# minime_2_1.net
KiCad netlist of a schematic drawn in EAGLE
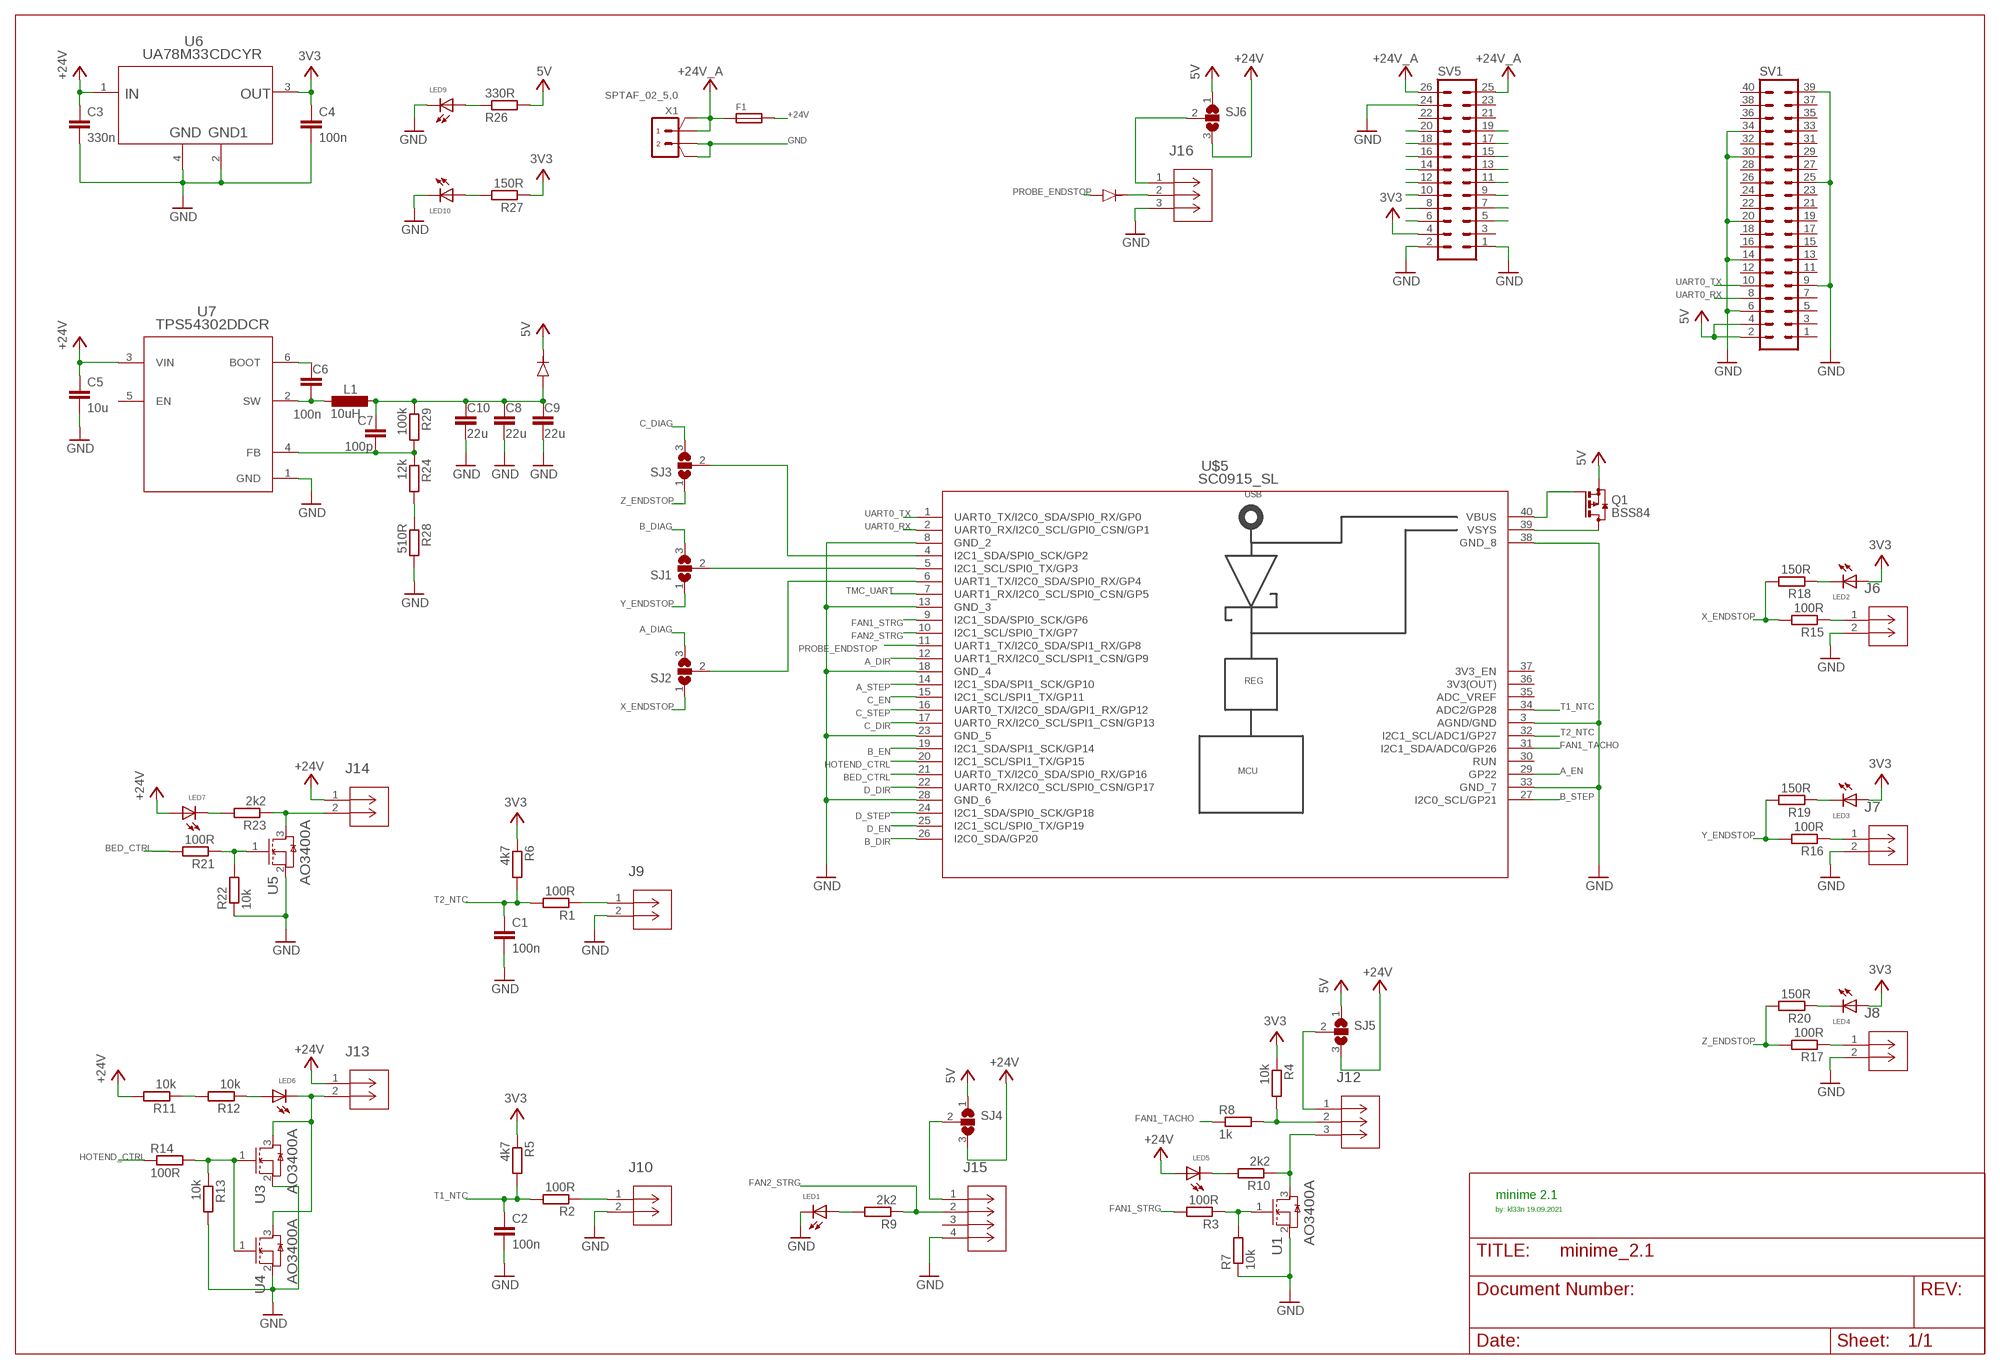
[diagram p0: schematic, sheet 1]

(export (version "E")
  (design (tool "Eeschema 10.0.6"))
  (components
    (comp (ref "C1")
      (value "100n")
      (footprint "eagle-import:C0603")
      (libsource (lib "eagle-import") (part "C-EUC0603"))
    )
    (comp (ref "C2")
      (value "100n")
      (footprint "eagle-import:C0603")
      (libsource (lib "eagle-import") (part "C-EUC0603"))
    )
    (comp (ref "C3")
      (value "330n")
      (footprint "eagle-import:C0603")
      (libsource (lib "eagle-import") (part "C-EUC0603"))
    )
    (comp (ref "C4")
      (value "100n")
      (footprint "eagle-import:C0603")
      (libsource (lib "eagle-import") (part "C-EUC0603"))
    )
    (comp (ref "C5")
      (value "10u")
      (footprint "eagle-import:C0603")
      (libsource (lib "eagle-import") (part "C-EUC0603"))
    )
    (comp (ref "C6")
      (value "100n")
      (footprint "eagle-import:C0603")
      (libsource (lib "eagle-import") (part "C-EUC0603"))
    )
    (comp (ref "C7")
      (value "100p")
      (footprint "eagle-import:C0603")
      (libsource (lib "eagle-import") (part "C-EUC0603"))
    )
    (comp (ref "C8")
      (value "22u")
      (footprint "eagle-import:C0603")
      (libsource (lib "eagle-import") (part "C-EUC0603"))
    )
    (comp (ref "C9")
      (value "22u")
      (footprint "eagle-import:C0603")
      (libsource (lib "eagle-import") (part "C-EUC0603"))
    )
    (comp (ref "C10")
      (value "22u")
      (footprint "eagle-import:C0603")
      (libsource (lib "eagle-import") (part "C-EUC0603"))
    )
    (comp (ref "CR1")
      (value "SS54")
      (footprint "eagle-import:DIODE_DO214AC")
      (fields
        (field (name "MANUFACTURER_PART_NUMBER") "SS14-E3/5AT")
        (field (name "COPYRIGHT") "Copyright (C) 2021 Ultra Librarian. All rights reserved.")
      )
      (libsource (lib "eagle-import") (part "SS14-E3/5AT"))
    )
    (comp (ref "CR2")
      (value "SS14")
      (footprint "eagle-import:DIODE_DO214AC")
      (fields
        (field (name "MANUFACTURER_PART_NUMBER") "SS14-E3/5AT")
        (field (name "COPYRIGHT") "Copyright (C) 2021 Ultra Librarian. All rights reserved.")
      )
      (libsource (lib "eagle-import") (part "SS14-E3/5AT"))
    )
    (comp (ref "F1")
      (value "FUSE/SERIE154")
      (footprint "eagle-import:FUSE_NANO-OMNI")
      (libsource (lib "eagle-import") (part "FUSE/SERIE154"))
    )
    (comp (ref "J6")
      (value "B2B-XH-A(LF)(SN)")
      (footprint "eagle-import:CONN_B2B-XH-A(LF)(SN)_JST")
      (fields (field (name "COPYRIGHT") "Copyright (C) 2018 Accelerated Designs. All rights reserved"))
      (libsource (lib "eagle-import") (part "B2B-XH-A(LF)(SN)"))
    )
    (comp (ref "J7")
      (value "B2B-XH-A(LF)(SN)")
      (footprint "eagle-import:CONN_B2B-XH-A(LF)(SN)_JST")
      (fields (field (name "COPYRIGHT") "Copyright (C) 2018 Accelerated Designs. All rights reserved"))
      (libsource (lib "eagle-import") (part "B2B-XH-A(LF)(SN)"))
    )
    (comp (ref "J8")
      (value "B2B-XH-A(LF)(SN)")
      (footprint "eagle-import:CONN_B2B-XH-A(LF)(SN)_JST")
      (fields (field (name "COPYRIGHT") "Copyright (C) 2018 Accelerated Designs. All rights reserved"))
      (libsource (lib "eagle-import") (part "B2B-XH-A(LF)(SN)"))
    )
    (comp (ref "J9")
      (value "B2B-XH-A(LF)(SN)")
      (footprint "eagle-import:CONN_B2B-XH-A(LF)(SN)_JST")
      (fields (field (name "COPYRIGHT") "Copyright (C) 2018 Accelerated Designs. All rights reserved"))
      (libsource (lib "eagle-import") (part "B2B-XH-A(LF)(SN)"))
    )
    (comp (ref "J10")
      (value "B2B-XH-A(LF)(SN)")
      (footprint "eagle-import:CONN_B2B-XH-A(LF)(SN)_JST")
      (fields (field (name "COPYRIGHT") "Copyright (C) 2018 Accelerated Designs. All rights reserved"))
      (libsource (lib "eagle-import") (part "B2B-XH-A(LF)(SN)"))
    )
    (comp (ref "J12")
      (value "B3B-XH-A(LF)(SN)")
      (footprint "eagle-import:CONN_B3B-XH-A_JST")
      (fields (field (name "COPYRIGHT") "Copyright (C) 2018 Accelerated Designs. All rights reserved"))
      (libsource (lib "eagle-import") (part "B3B-XH-A(LF)(SN)"))
    )
    (comp (ref "J13")
      (value "B2B-XH-A(LF)(SN)")
      (footprint "eagle-import:CONN_B2B-XH-A(LF)(SN)_JST")
      (fields (field (name "COPYRIGHT") "Copyright (C) 2018 Accelerated Designs. All rights reserved"))
      (libsource (lib "eagle-import") (part "B2B-XH-A(LF)(SN)"))
    )
    (comp (ref "J14")
      (value "B2B-XH-A(LF)(SN)")
      (footprint "eagle-import:CONN_B2B-XH-A(LF)(SN)_JST")
      (fields (field (name "COPYRIGHT") "Copyright (C) 2018 Accelerated Designs. All rights reserved"))
      (libsource (lib "eagle-import") (part "B2B-XH-A(LF)(SN)"))
    )
    (comp (ref "J15")
      (value "B4B-XH-AM(LF)(SN)")
      (footprint "eagle-import:CONN_B4B-XH-AM_JST")
      (fields (field (name "COPYRIGHT") "Copyright (C) 2018 Accelerated Designs. All rights reserved"))
      (libsource (lib "eagle-import") (part "B4B-XH-AM(LF)(SN)"))
    )
    (comp (ref "J16")
      (value "B3B-XH-A(LF)(SN)")
      (footprint "eagle-import:CONN_B3B-XH-A_JST")
      (fields (field (name "COPYRIGHT") "Copyright (C) 2018 Accelerated Designs. All rights reserved"))
      (libsource (lib "eagle-import") (part "B3B-XH-A(LF)(SN)"))
    )
    (comp (ref "L1")
      (value "10uH")
      (footprint "eagle-import:POWER-CHOKE_WE-TPC")
      (libsource (lib "eagle-import") (part "L-EUWE-TPC"))
    )
    (comp (ref "LED1")
      (value "LEDCHIP-LED0603")
      (footprint "eagle-import:CHIP-LED0603")
      (libsource (lib "eagle-import") (part "LEDCHIP-LED0603"))
    )
    (comp (ref "LED2")
      (value "LEDCHIP-LED0603")
      (footprint "eagle-import:CHIP-LED0603")
      (libsource (lib "eagle-import") (part "LEDCHIP-LED0603"))
    )
    (comp (ref "LED3")
      (value "LEDCHIP-LED0603")
      (footprint "eagle-import:CHIP-LED0603")
      (libsource (lib "eagle-import") (part "LEDCHIP-LED0603"))
    )
    (comp (ref "LED4")
      (value "LEDCHIP-LED0603")
      (footprint "eagle-import:CHIP-LED0603")
      (libsource (lib "eagle-import") (part "LEDCHIP-LED0603"))
    )
    (comp (ref "LED5")
      (value "LEDCHIP-LED0603")
      (footprint "eagle-import:CHIP-LED0603")
      (libsource (lib "eagle-import") (part "LEDCHIP-LED0603"))
    )
    (comp (ref "LED6")
      (value "LEDCHIP-LED0603")
      (footprint "eagle-import:CHIP-LED0603")
      (libsource (lib "eagle-import") (part "LEDCHIP-LED0603"))
    )
    (comp (ref "LED7")
      (value "LEDCHIP-LED0603")
      (footprint "eagle-import:CHIP-LED0603")
      (libsource (lib "eagle-import") (part "LEDCHIP-LED0603"))
    )
    (comp (ref "LED9")
      (value "LEDCHIP-LED0603")
      (footprint "eagle-import:CHIP-LED0603")
      (libsource (lib "eagle-import") (part "LEDCHIP-LED0603"))
    )
    (comp (ref "LED10")
      (value "LEDCHIP-LED0603")
      (footprint "eagle-import:CHIP-LED0603")
      (libsource (lib "eagle-import") (part "LEDCHIP-LED0603"))
    )
    (comp (ref "Q1")
      (value "BSS84")
      (footprint "eagle-import:SOT23")
      (libsource (lib "eagle-import") (part "BSS84"))
    )
    (comp (ref "R1")
      (value "100R")
      (footprint "eagle-import:R0603")
      (libsource (lib "eagle-import") (part "R-EU_R0603"))
    )
    (comp (ref "R2")
      (value "100R")
      (footprint "eagle-import:R0603")
      (libsource (lib "eagle-import") (part "R-EU_R0603"))
    )
    (comp (ref "R3")
      (value "100R")
      (footprint "eagle-import:R0603")
      (libsource (lib "eagle-import") (part "R-EU_R0603"))
    )
    (comp (ref "R4")
      (value "10k")
      (footprint "eagle-import:R0603")
      (libsource (lib "eagle-import") (part "R-EU_R0603"))
    )
    (comp (ref "R5")
      (value "4k7")
      (footprint "eagle-import:R0603")
      (libsource (lib "eagle-import") (part "R-EU_R0603"))
    )
    (comp (ref "R6")
      (value "4k7")
      (footprint "eagle-import:R0603")
      (libsource (lib "eagle-import") (part "R-EU_R0603"))
    )
    (comp (ref "R7")
      (value "10k")
      (footprint "eagle-import:R0603")
      (libsource (lib "eagle-import") (part "R-EU_R0603"))
    )
    (comp (ref "R8")
      (value "1k")
      (footprint "eagle-import:R0603")
      (libsource (lib "eagle-import") (part "R-EU_R0603"))
    )
    (comp (ref "R9")
      (value "2k2")
      (footprint "eagle-import:R0603")
      (libsource (lib "eagle-import") (part "R-EU_R0603"))
    )
    (comp (ref "R10")
      (value "2k2")
      (footprint "eagle-import:R0603")
      (libsource (lib "eagle-import") (part "R-EU_R0603"))
    )
    (comp (ref "R11")
      (value "10k")
      (footprint "eagle-import:R0603")
      (libsource (lib "eagle-import") (part "R-EU_R0603"))
    )
    (comp (ref "R12")
      (value "10k")
      (footprint "eagle-import:R0603")
      (libsource (lib "eagle-import") (part "R-EU_R0603"))
    )
    (comp (ref "R13")
      (value "10k")
      (footprint "eagle-import:R0603")
      (libsource (lib "eagle-import") (part "R-EU_R0603"))
    )
    (comp (ref "R14")
      (value "100R")
      (footprint "eagle-import:R0603")
      (libsource (lib "eagle-import") (part "R-EU_R0603"))
    )
    (comp (ref "R15")
      (value "100R")
      (footprint "eagle-import:R0603")
      (libsource (lib "eagle-import") (part "R-EU_R0603"))
    )
    (comp (ref "R16")
      (value "100R")
      (footprint "eagle-import:R0603")
      (libsource (lib "eagle-import") (part "R-EU_R0603"))
    )
    (comp (ref "R17")
      (value "100R")
      (footprint "eagle-import:R0603")
      (libsource (lib "eagle-import") (part "R-EU_R0603"))
    )
    (comp (ref "R18")
      (value "150R")
      (footprint "eagle-import:R0603")
      (libsource (lib "eagle-import") (part "R-EU_R0603"))
    )
    (comp (ref "R19")
      (value "150R")
      (footprint "eagle-import:R0603")
      (libsource (lib "eagle-import") (part "R-EU_R0603"))
    )
    (comp (ref "R20")
      (value "150R")
      (footprint "eagle-import:R0603")
      (libsource (lib "eagle-import") (part "R-EU_R0603"))
    )
    (comp (ref "R21")
      (value "100R")
      (footprint "eagle-import:R0603")
      (libsource (lib "eagle-import") (part "R-EU_R0603"))
    )
    (comp (ref "R22")
      (value "10k")
      (footprint "eagle-import:R0603")
      (libsource (lib "eagle-import") (part "R-EU_R0603"))
    )
    (comp (ref "R23")
      (value "2k2")
      (footprint "eagle-import:R0603")
      (libsource (lib "eagle-import") (part "R-EU_R0603"))
    )
    (comp (ref "R24")
      (value "12k")
      (footprint "eagle-import:R0603")
      (libsource (lib "eagle-import") (part "R-EU_R0603"))
    )
    (comp (ref "R26")
      (value "330R")
      (footprint "eagle-import:R0603")
      (libsource (lib "eagle-import") (part "R-EU_R0603"))
    )
    (comp (ref "R27")
      (value "150R")
      (footprint "eagle-import:R0603")
      (libsource (lib "eagle-import") (part "R-EU_R0603"))
    )
    (comp (ref "R28")
      (value "510R")
      (footprint "eagle-import:R0603")
      (libsource (lib "eagle-import") (part "R-EU_R0603"))
    )
    (comp (ref "R29")
      (value "100k")
      (footprint "eagle-import:R0603")
      (libsource (lib "eagle-import") (part "R-EU_R0603"))
    )
    (comp (ref "SJ1")
      (value "SJ2W")
      (footprint "eagle-import:SJ_2")
      (libsource (lib "eagle-import") (part "SJ2W"))
    )
    (comp (ref "SJ2")
      (value "SJ2W")
      (footprint "eagle-import:SJ_2")
      (libsource (lib "eagle-import") (part "SJ2W"))
    )
    (comp (ref "SJ3")
      (value "SJ2W")
      (footprint "eagle-import:SJ_2")
      (libsource (lib "eagle-import") (part "SJ2W"))
    )
    (comp (ref "SJ4")
      (value "SJ2W")
      (footprint "eagle-import:SJ_2")
      (libsource (lib "eagle-import") (part "SJ2W"))
    )
    (comp (ref "SJ5")
      (value "SJ2W")
      (footprint "eagle-import:SJ_2")
      (libsource (lib "eagle-import") (part "SJ2W"))
    )
    (comp (ref "SJ6")
      (value "SJ2W")
      (footprint "eagle-import:SJ_2")
      (libsource (lib "eagle-import") (part "SJ2W"))
    )
    (comp (ref "SV1")
      (value "MA20-2")
      (footprint "eagle-import:MA20-2")
      (libsource (lib "eagle-import") (part "MA20-2"))
    )
    (comp (ref "SV5")
      (value "MA13-2")
      (footprint "eagle-import:MA13-2")
      (libsource (lib "eagle-import") (part "MA13-2"))
    )
    (comp (ref "U$5")
      (value "SC0915_SL")
      (footprint "eagle-import:STIFTLEISTE")
      (libsource (lib "eagle-import") (part "SC0915_SL"))
    )
    (comp (ref "U1")
      (value "AO3400A")
      (footprint "eagle-import:SOT-23-3L_AOS")
      (fields (field (name "COPYRIGHT") "Copyright (C) 2018 Accelerated Designs. All rights reserved"))
      (libsource (lib "eagle-import") (part "AO3400A"))
    )
    (comp (ref "U3")
      (value "AO3400A")
      (footprint "eagle-import:SOT-23-3L_AOS")
      (fields (field (name "COPYRIGHT") "Copyright (C) 2018 Accelerated Designs. All rights reserved"))
      (libsource (lib "eagle-import") (part "AO3400A"))
    )
    (comp (ref "U4")
      (value "AO3400A")
      (footprint "eagle-import:SOT-23-3L_AOS")
      (fields (field (name "COPYRIGHT") "Copyright (C) 2018 Accelerated Designs. All rights reserved"))
      (libsource (lib "eagle-import") (part "AO3400A"))
    )
    (comp (ref "U5")
      (value "AO3400A")
      (footprint "eagle-import:SOT-23-3L_AOS")
      (fields (field (name "COPYRIGHT") "Copyright (C) 2018 Accelerated Designs. All rights reserved"))
      (libsource (lib "eagle-import") (part "AO3400A"))
    )
    (comp (ref "U6")
      (value "UA78M33CDCYR")
      (footprint "eagle-import:DCY0004A_N")
      (fields (field (name "COPYRIGHT") "Copyright (C) 2021 Ultra Librarian. All rights reserved."))
      (libsource (lib "eagle-import") (part "UA78M33CDCYR"))
    )
    (comp (ref "U7")
      (value "TPS54302DDCR")
      (footprint "eagle-import:DDC0006A_N")
      (fields (field (name "COPYRIGHT") "Copyright (C) 2021 Ultra Librarian. All rights reserved."))
      (libsource (lib "eagle-import") (part "TPS54302DDCR"))
    )
    (comp (ref "X1")
      (value "SPTAF_02_5,0")
      (footprint "eagle-import:5-2")
      (libsource (lib "eagle-import") (part "SPTAF_02_5,0"))
    )
  )
  (nets
    (net (code "1") (name "+24V") (class "Default")
      (node (ref "C3") (pin "1") (pinfunction "1_1") (pintype "passive"))
      (node (ref "C5") (pin "1") (pinfunction "1_1") (pintype "passive"))
      (node (ref "F1") (pin "2") (pinfunction "2_2") (pintype "passive"))
      (node (ref "J13") (pin "1") (pinfunction "1_1") (pintype "passive"))
      (node (ref "J14") (pin "1") (pinfunction "1_1") (pintype "passive"))
      (node (ref "LED5") (pin "A") (pinfunction "A_A") (pintype "passive"))
      (node (ref "LED7") (pin "A") (pinfunction "A_A") (pintype "passive"))
      (node (ref "R11") (pin "2") (pinfunction "2_2") (pintype "passive"))
      (node (ref "SJ4") (pin "3") (pinfunction "3_3") (pintype "passive"))
      (node (ref "SJ5") (pin "3") (pinfunction "3_3") (pintype "passive"))
      (node (ref "SJ6") (pin "3") (pinfunction "3_3") (pintype "passive"))
      (node (ref "U6") (pin "1") (pinfunction "INPUT_1") (pintype "power_in"))
      (node (ref "U7") (pin "3") (pinfunction "VIN_3") (pintype "power_in"))
    )
    (net (code "2") (name "+24V_A") (class "Default")
      (node (ref "F1") (pin "1") (pinfunction "1_1") (pintype "passive"))
      (node (ref "SV5") (pin "25") (pinfunction "25_25") (pintype "passive"))
      (node (ref "SV5") (pin "26") (pinfunction "26_26") (pintype "passive"))
      (node (ref "X1") (pin "1") (pinfunction "1_1") (pintype "passive"))
      (node (ref "X1") (pin "1A") (pinfunction "1A_1A") (pintype "passive"))
    )
    (net (code "3") (name "/3V3_EN") (class "Default")
      (node (ref "U$5") (pin "37") (pinfunction "3V3_EN_37") (pintype "power_in"))
    )
    (net (code "4") (name "/ADC_VREF") (class "Default")
      (node (ref "U$5") (pin "35") (pinfunction "ADC_VREF_35") (pintype "power_in"))
    )
    (net (code "5") (name "/A_DIAG") (class "Default")
      (node (ref "SJ2") (pin "3") (pinfunction "3_3") (pintype "passive"))
      (node (ref "SV5") (pin "5") (pinfunction "5_5") (pintype "passive"))
    )
    (net (code "6") (name "/A_DIR") (class "Default")
      (node (ref "SV5") (pin "8") (pinfunction "8_8") (pintype "passive"))
      (node (ref "U$5") (pin "12") (pinfunction "UART1_RX/I2C0_SCL/SPI1_CSN/GP9_12") (pintype "bidirectional"))
    )
    (net (code "7") (name "/A_EN") (class "Default")
      (node (ref "SV5") (pin "6") (pinfunction "6_6") (pintype "passive"))
      (node (ref "U$5") (pin "29") (pinfunction "GP22_29") (pintype "bidirectional"))
    )
    (net (code "8") (name "/A_STEP") (class "Default")
      (node (ref "SV5") (pin "7") (pinfunction "7_7") (pintype "passive"))
      (node (ref "U$5") (pin "14") (pinfunction "I2C1_SDA/SPI1_SCK/GP10_14") (pintype "bidirectional"))
    )
    (net (code "9") (name "/BED_CTRL") (class "Default")
      (node (ref "R21") (pin "2") (pinfunction "2_2") (pintype "passive"))
      (node (ref "U$5") (pin "21") (pinfunction "UART0_TX/I2C0_SDA/SPI0_RX/GP16_21") (pintype "bidirectional"))
    )
    (net (code "10") (name "/B_DIAG") (class "Default")
      (node (ref "SJ1") (pin "3") (pinfunction "3_3") (pintype "passive"))
      (node (ref "SV5") (pin "14") (pinfunction "14_14") (pintype "passive"))
    )
    (net (code "11") (name "/B_DIR") (class "Default")
      (node (ref "SV5") (pin "17") (pinfunction "17_17") (pintype "passive"))
      (node (ref "U$5") (pin "26") (pinfunction "I2C0_SDA/GP20_26") (pintype "bidirectional"))
    )
    (net (code "12") (name "/B_EN") (class "Default")
      (node (ref "SV5") (pin "15") (pinfunction "15_15") (pintype "passive"))
      (node (ref "U$5") (pin "19") (pinfunction "I2C1_SDA/SPI1_SCK/GP14_19") (pintype "bidirectional"))
    )
    (net (code "13") (name "/B_STEP") (class "Default")
      (node (ref "SV5") (pin "16") (pinfunction "16_16") (pintype "passive"))
      (node (ref "U$5") (pin "27") (pinfunction "I2C0_SCL/GP21_27") (pintype "bidirectional"))
    )
    (net (code "14") (name "/C_DIAG") (class "Default")
      (node (ref "SJ3") (pin "3") (pinfunction "3_3") (pintype "passive"))
      (node (ref "SV5") (pin "9") (pinfunction "9_9") (pintype "passive"))
    )
    (net (code "15") (name "/C_DIR") (class "Default")
      (node (ref "SV5") (pin "12") (pinfunction "12_12") (pintype "passive"))
      (node (ref "U$5") (pin "17") (pinfunction "UART0_RX/I2C0_SCL/SPI1_CSN/GP13_17") (pintype "bidirectional"))
    )
    (net (code "16") (name "/C_EN") (class "Default")
      (node (ref "SV5") (pin "10") (pinfunction "10_10") (pintype "passive"))
      (node (ref "U$5") (pin "15") (pinfunction "I2C1_SCL/SPI1_TX/GP11_15") (pintype "bidirectional"))
    )
    (net (code "17") (name "/C_STEP") (class "Default")
      (node (ref "SV5") (pin "11") (pinfunction "11_11") (pintype "passive"))
      (node (ref "U$5") (pin "16") (pinfunction "UART0_TX/I2C0_SDA/GPI1_RX/GP12_16") (pintype "bidirectional"))
    )
    (net (code "18") (name "/D_DIR") (class "Default")
      (node (ref "SV5") (pin "20") (pinfunction "20_20") (pintype "passive"))
      (node (ref "U$5") (pin "22") (pinfunction "UART0_RX/I2C0_SCL/SPI0_CSN/GP17_22") (pintype "bidirectional"))
    )
    (net (code "19") (name "/D_EN") (class "Default")
      (node (ref "SV5") (pin "18") (pinfunction "18_18") (pintype "passive"))
      (node (ref "U$5") (pin "25") (pinfunction "I2C1_SCL/SPI0_TX/GP19_25") (pintype "bidirectional"))
    )
    (net (code "20") (name "/D_STEP") (class "Default")
      (node (ref "SV5") (pin "19") (pinfunction "19_19") (pintype "passive"))
      (node (ref "U$5") (pin "24") (pinfunction "I2C1_SDA/SPI0_SCK/GP18_24") (pintype "bidirectional"))
    )
    (net (code "21") (name "/FAN1_STRG") (class "Default")
      (node (ref "R3") (pin "2") (pinfunction "2_2") (pintype "passive"))
      (node (ref "U$5") (pin "9") (pinfunction "I2C1_SDA/SPI0_SCK/GP6_9") (pintype "bidirectional"))
    )
    (net (code "22") (name "/FAN1_TACHO") (class "Default")
      (node (ref "R8") (pin "1") (pinfunction "1_1") (pintype "passive"))
      (node (ref "U$5") (pin "31") (pinfunction "I2C1_SDA/ADC0/GP26_31") (pintype "bidirectional"))
    )
    (net (code "23") (name "/FAN2_STRG") (class "Default")
      (node (ref "J15") (pin "2") (pinfunction "2_2") (pintype "passive"))
      (node (ref "R9") (pin "1") (pinfunction "1_1") (pintype "passive"))
      (node (ref "U$5") (pin "10") (pinfunction "I2C1_SCL/SPI0_TX/GP7_10") (pintype "bidirectional"))
    )
    (net (code "24") (name "/HOTEND_CTRL") (class "Default")
      (node (ref "R14") (pin "1") (pinfunction "1_1") (pintype "passive"))
      (node (ref "U$5") (pin "20") (pinfunction "I2C1_SCL/SPI1_TX/GP15_20") (pintype "bidirectional"))
    )
    (net (code "25") (name "/PROBE_ENDSTOP") (class "Default")
      (node (ref "CR2") (pin "2") (pinfunction "2_2") (pintype "passive"))
      (node (ref "U$5") (pin "11") (pinfunction "UART1_TX/I2C0_SDA/SPI1_RX/GP8_11") (pintype "bidirectional"))
    )
    (net (code "26") (name "/T1_NTC") (class "Default")
      (node (ref "C2") (pin "1") (pinfunction "1_1") (pintype "passive"))
      (node (ref "R2") (pin "2") (pinfunction "2_2") (pintype "passive"))
      (node (ref "R5") (pin "2") (pinfunction "2_2") (pintype "passive"))
      (node (ref "U$5") (pin "34") (pinfunction "ADC2/GP28_34") (pintype "bidirectional"))
    )
    (net (code "27") (name "/T2_NTC") (class "Default")
      (node (ref "C1") (pin "1") (pinfunction "1_1") (pintype "passive"))
      (node (ref "R1") (pin "2") (pinfunction "2_2") (pintype "passive"))
      (node (ref "R6") (pin "2") (pinfunction "2_2") (pintype "passive"))
      (node (ref "U$5") (pin "32") (pinfunction "I2C1_SCL/ADC1/GP27_32") (pintype "bidirectional"))
    )
    (net (code "28") (name "/TMC_UART") (class "Default")
      (node (ref "SV5") (pin "13") (pinfunction "13_13") (pintype "passive"))
      (node (ref "U$5") (pin "7") (pinfunction "UART1_RX/I2C0_SCL/SPI0_CSN/GP5_7") (pintype "bidirectional"))
    )
    (net (code "29") (name "/UART0_RX") (class "Default")
      (node (ref "SV1") (pin "8") (pinfunction "8_8") (pintype "passive"))
      (node (ref "U$5") (pin "2") (pinfunction "UART0_RX/I2C0_SCL/GPI0_CSN/GP1_2") (pintype "bidirectional"))
    )
    (net (code "30") (name "/UART0_TX") (class "Default")
      (node (ref "SV1") (pin "10") (pinfunction "10_10") (pintype "passive"))
      (node (ref "U$5") (pin "1") (pinfunction "UART0_TX/I2C0_SDA/SPI0_RX/GP0_1") (pintype "bidirectional"))
    )
    (net (code "31") (name "/X_ENDSTOP") (class "Default")
      (node (ref "R15") (pin "2") (pinfunction "2_2") (pintype "passive"))
      (node (ref "R18") (pin "2") (pinfunction "2_2") (pintype "passive"))
      (node (ref "SJ2") (pin "1") (pinfunction "1_1") (pintype "passive"))
    )
    (net (code "32") (name "/Y_ENDSTOP") (class "Default")
      (node (ref "R16") (pin "2") (pinfunction "2_2") (pintype "passive"))
      (node (ref "R19") (pin "2") (pinfunction "2_2") (pintype "passive"))
      (node (ref "SJ1") (pin "1") (pinfunction "1_1") (pintype "passive"))
    )
    (net (code "33") (name "/Z_ENDSTOP") (class "Default")
      (node (ref "R17") (pin "2") (pinfunction "2_2") (pintype "passive"))
      (node (ref "R20") (pin "2") (pinfunction "2_2") (pintype "passive"))
      (node (ref "SJ3") (pin "1") (pinfunction "1_1") (pintype "passive"))
    )
    (net (code "34") (name "3V3") (class "Default")
      (node (ref "C4") (pin "1") (pinfunction "1_1") (pintype "passive"))
      (node (ref "LED2") (pin "A") (pinfunction "A_A") (pintype "passive"))
      (node (ref "LED3") (pin "A") (pinfunction "A_A") (pintype "passive"))
      (node (ref "LED4") (pin "A") (pinfunction "A_A") (pintype "passive"))
      (node (ref "R27") (pin "1") (pinfunction "1_1") (pintype "passive"))
      (node (ref "R4") (pin "1") (pinfunction "1_1") (pintype "passive"))
      (node (ref "R5") (pin "1") (pinfunction "1_1") (pintype "passive"))
      (node (ref "R6") (pin "1") (pinfunction "1_1") (pintype "passive"))
      (node (ref "SV5") (pin "4") (pinfunction "4_4") (pintype "passive"))
      (node (ref "U6") (pin "3") (pinfunction "OUTPUT_3") (pintype "power_in"))
    )
    (net (code "35") (name "5V") (class "Default")
      (node (ref "CR1") (pin "1") (pinfunction "1_1") (pintype "passive"))
      (node (ref "Q1") (pin "2") (pinfunction "S_2") (pintype "passive"))
      (node (ref "R26") (pin "2") (pinfunction "2_2") (pintype "passive"))
      (node (ref "SJ4") (pin "1") (pinfunction "1_1") (pintype "passive"))
      (node (ref "SJ5") (pin "1") (pinfunction "1_1") (pintype "passive"))
      (node (ref "SJ6") (pin "1") (pinfunction "1_1") (pintype "passive"))
      (node (ref "SV1") (pin "2") (pinfunction "2_2") (pintype "passive"))
      (node (ref "SV1") (pin "4") (pinfunction "4_4") (pintype "passive"))
    )
    (net (code "36") (name "GND") (class "Default")
      (node (ref "C1") (pin "2") (pinfunction "2_2") (pintype "passive"))
      (node (ref "C10") (pin "2") (pinfunction "2_2") (pintype "passive"))
      (node (ref "C2") (pin "2") (pinfunction "2_2") (pintype "passive"))
      (node (ref "C3") (pin "2") (pinfunction "2_2") (pintype "passive"))
      (node (ref "C4") (pin "2") (pinfunction "2_2") (pintype "passive"))
      (node (ref "C5") (pin "2") (pinfunction "2_2") (pintype "passive"))
      (node (ref "C8") (pin "2") (pinfunction "2_2") (pintype "passive"))
      (node (ref "C9") (pin "2") (pinfunction "2_2") (pintype "passive"))
      (node (ref "J10") (pin "2") (pinfunction "2_2") (pintype "passive"))
      (node (ref "J15") (pin "4") (pinfunction "4_4") (pintype "passive"))
      (node (ref "J16") (pin "3") (pinfunction "3_3") (pintype "passive"))
      (node (ref "J6") (pin "2") (pinfunction "2_2") (pintype "passive"))
      (node (ref "J7") (pin "2") (pinfunction "2_2") (pintype "passive"))
      (node (ref "J8") (pin "2") (pinfunction "2_2") (pintype "passive"))
      (node (ref "J9") (pin "2") (pinfunction "2_2") (pintype "passive"))
      (node (ref "LED1") (pin "C") (pinfunction "C_C") (pintype "passive"))
      (node (ref "LED10") (pin "C") (pinfunction "C_C") (pintype "passive"))
      (node (ref "LED9") (pin "C") (pinfunction "C_C") (pintype "passive"))
      (node (ref "R13") (pin "2") (pinfunction "2_2") (pintype "passive"))
      (node (ref "R22") (pin "1") (pinfunction "1_1") (pintype "passive"))
      (node (ref "R28") (pin "2") (pinfunction "2_2") (pintype "passive"))
      (node (ref "R7") (pin "1") (pinfunction "1_1") (pintype "passive"))
      (node (ref "SV1") (pin "14") (pinfunction "14_14") (pintype "passive"))
      (node (ref "SV1") (pin "20") (pinfunction "20_20") (pintype "passive"))
      (node (ref "SV1") (pin "25") (pinfunction "25_25") (pintype "passive"))
      (node (ref "SV1") (pin "30") (pinfunction "30_30") (pintype "passive"))
      (node (ref "SV1") (pin "34") (pinfunction "34_34") (pintype "passive"))
      (node (ref "SV1") (pin "39") (pinfunction "39_39") (pintype "passive"))
      (node (ref "SV1") (pin "6") (pinfunction "6_6") (pintype "passive"))
      (node (ref "SV1") (pin "9") (pinfunction "9_9") (pintype "passive"))
      (node (ref "SV5") (pin "1") (pinfunction "1_1") (pintype "passive"))
      (node (ref "SV5") (pin "2") (pinfunction "2_2") (pintype "passive"))
      (node (ref "SV5") (pin "24") (pinfunction "24_24") (pintype "passive"))
      (node (ref "U$5") (pin "13") (pinfunction "GND_3_13") (pintype "passive"))
      (node (ref "U$5") (pin "18") (pinfunction "GND_4_18") (pintype "passive"))
      (node (ref "U$5") (pin "23") (pinfunction "GND_5_23") (pintype "passive"))
      (node (ref "U$5") (pin "28") (pinfunction "GND_6_28") (pintype "passive"))
      (node (ref "U$5") (pin "3") (pinfunction "AGND/GND_3") (pintype "passive"))
      (node (ref "U$5") (pin "33") (pinfunction "GND_7_33") (pintype "passive"))
      (node (ref "U$5") (pin "38") (pinfunction "GND_8_38") (pintype "passive"))
      (node (ref "U$5") (pin "8") (pinfunction "GND_2_8") (pintype "passive"))
      (node (ref "U1") (pin "2") (pinfunction "S_2") (pintype "passive"))
      (node (ref "U3") (pin "2") (pinfunction "S_2") (pintype "passive"))
      (node (ref "U4") (pin "2") (pinfunction "S_2") (pintype "passive"))
      (node (ref "U5") (pin "2") (pinfunction "S_2") (pintype "passive"))
      (node (ref "U6") (pin "2") (pinfunction "COMMON_2_2") (pintype "power_in"))
      (node (ref "U6") (pin "4") (pinfunction "COMMON_4") (pintype "power_in"))
      (node (ref "U7") (pin "1") (pinfunction "GND_1") (pintype "power_in"))
      (node (ref "X1") (pin "2") (pinfunction "2_2") (pintype "passive"))
      (node (ref "X1") (pin "2A") (pinfunction "2A_2A") (pintype "passive"))
    )
    (net (code "37") (name "Net-(C10-Pad1)") (class "Default")
      (node (ref "C10") (pin "1") (pinfunction "1_1") (pintype "passive"))
      (node (ref "C7") (pin "1") (pinfunction "1_1") (pintype "passive"))
      (node (ref "C8") (pin "1") (pinfunction "1_1") (pintype "passive"))
      (node (ref "C9") (pin "1") (pinfunction "1_1") (pintype "passive"))
      (node (ref "CR1") (pin "2") (pinfunction "2_2") (pintype "passive"))
      (node (ref "L1") (pin "1") (pinfunction "1_1") (pintype "passive"))
      (node (ref "R29") (pin "1") (pinfunction "1_1") (pintype "passive"))
    )
    (net (code "38") (name "Net-(CR2-Pad1)") (class "Default")
      (node (ref "CR2") (pin "1") (pinfunction "1_1") (pintype "passive"))
      (node (ref "J16") (pin "2") (pinfunction "2_2") (pintype "passive"))
    )
    (net (code "39") (name "Net-(J6-Pad1)") (class "Default")
      (node (ref "J6") (pin "1") (pinfunction "1_1") (pintype "passive"))
      (node (ref "R15") (pin "1") (pinfunction "1_1") (pintype "passive"))
    )
    (net (code "40") (name "Net-(J7-Pad1)") (class "Default")
      (node (ref "J7") (pin "1") (pinfunction "1_1") (pintype "passive"))
      (node (ref "R16") (pin "1") (pinfunction "1_1") (pintype "passive"))
    )
    (net (code "41") (name "Net-(J8-Pad1)") (class "Default")
      (node (ref "J8") (pin "1") (pinfunction "1_1") (pintype "passive"))
      (node (ref "R17") (pin "1") (pinfunction "1_1") (pintype "passive"))
    )
    (net (code "42") (name "Net-(J9-Pad1)") (class "Default")
      (node (ref "J9") (pin "1") (pinfunction "1_1") (pintype "passive"))
      (node (ref "R1") (pin "1") (pinfunction "1_1") (pintype "passive"))
    )
    (net (code "43") (name "Net-(J10-Pad1)") (class "Default")
      (node (ref "J10") (pin "1") (pinfunction "1_1") (pintype "passive"))
      (node (ref "R2") (pin "1") (pinfunction "1_1") (pintype "passive"))
    )
    (net (code "44") (name "Net-(J12-Pad1)") (class "Default")
      (node (ref "J12") (pin "1") (pinfunction "1_1") (pintype "passive"))
      (node (ref "SJ5") (pin "2") (pinfunction "2_2") (pintype "passive"))
    )
    (net (code "45") (name "Net-(J12-Pad2)") (class "Default")
      (node (ref "J12") (pin "2") (pinfunction "2_2") (pintype "passive"))
      (node (ref "R4") (pin "2") (pinfunction "2_2") (pintype "passive"))
      (node (ref "R8") (pin "2") (pinfunction "2_2") (pintype "passive"))
    )
    (net (code "46") (name "Net-(J15-Pad1)") (class "Default")
      (node (ref "J15") (pin "1") (pinfunction "1_1") (pintype "passive"))
      (node (ref "SJ4") (pin "2") (pinfunction "2_2") (pintype "passive"))
    )
    (net (code "47") (name "Net-(J16-Pad1)") (class "Default")
      (node (ref "J16") (pin "1") (pinfunction "1_1") (pintype "passive"))
      (node (ref "SJ6") (pin "2") (pinfunction "2_2") (pintype "passive"))
    )
    (net (code "48") (name "Net-(LED1-PadA)") (class "Default")
      (node (ref "LED1") (pin "A") (pinfunction "A_A") (pintype "passive"))
      (node (ref "R9") (pin "2") (pinfunction "2_2") (pintype "passive"))
    )
    (net (code "49") (name "Net-(LED2-PadC)") (class "Default")
      (node (ref "LED2") (pin "C") (pinfunction "C_C") (pintype "passive"))
      (node (ref "R18") (pin "1") (pinfunction "1_1") (pintype "passive"))
    )
    (net (code "50") (name "Net-(LED3-PadC)") (class "Default")
      (node (ref "LED3") (pin "C") (pinfunction "C_C") (pintype "passive"))
      (node (ref "R19") (pin "1") (pinfunction "1_1") (pintype "passive"))
    )
    (net (code "51") (name "Net-(LED4-PadC)") (class "Default")
      (node (ref "LED4") (pin "C") (pinfunction "C_C") (pintype "passive"))
      (node (ref "R20") (pin "1") (pinfunction "1_1") (pintype "passive"))
    )
    (net (code "52") (name "Net-(LED5-PadC)") (class "Default")
      (node (ref "LED5") (pin "C") (pinfunction "C_C") (pintype "passive"))
      (node (ref "R10") (pin "2") (pinfunction "2_2") (pintype "passive"))
    )
    (net (code "53") (name "Net-(LED6-PadA)") (class "Default")
      (node (ref "LED6") (pin "A") (pinfunction "A_A") (pintype "passive"))
      (node (ref "R12") (pin "1") (pinfunction "1_1") (pintype "passive"))
    )
    (net (code "54") (name "Net-(LED7-PadC)") (class "Default")
      (node (ref "LED7") (pin "C") (pinfunction "C_C") (pintype "passive"))
      (node (ref "R23") (pin "2") (pinfunction "2_2") (pintype "passive"))
    )
    (net (code "55") (name "Net-(LED9-PadA)") (class "Default")
      (node (ref "LED9") (pin "A") (pinfunction "A_A") (pintype "passive"))
      (node (ref "R26") (pin "1") (pinfunction "1_1") (pintype "passive"))
    )
    (net (code "56") (name "Net-(LED10-PadA)") (class "Default")
      (node (ref "LED10") (pin "A") (pinfunction "A_A") (pintype "passive"))
      (node (ref "R27") (pin "2") (pinfunction "2_2") (pintype "passive"))
    )
    (net (code "57") (name "Net-(Q1-D)") (class "Default")
      (node (ref "Q1") (pin "3") (pinfunction "D_3") (pintype "passive"))
      (node (ref "U$5") (pin "39") (pinfunction "VSYS_39") (pintype "power_in"))
    )
    (net (code "58") (name "Net-(Q1-G)") (class "Default")
      (node (ref "Q1") (pin "1") (pinfunction "G_1") (pintype "passive"))
      (node (ref "U$5") (pin "40") (pinfunction "VBUS_40") (pintype "power_in"))
    )
    (net (code "59") (name "Net-(R11-Pad1)") (class "Default")
      (node (ref "R11") (pin "1") (pinfunction "1_1") (pintype "passive"))
      (node (ref "R12") (pin "2") (pinfunction "2_2") (pintype "passive"))
    )
    (net (code "60") (name "Net-(R24-Pad2)") (class "Default")
      (node (ref "R24") (pin "2") (pinfunction "2_2") (pintype "passive"))
      (node (ref "R28") (pin "1") (pinfunction "1_1") (pintype "passive"))
    )
    (net (code "61") (name "Net-(U$5-I2C1_SCL{slash}SPI0_TX{slash}GP3)") (class "Default")
      (node (ref "SJ1") (pin "2") (pinfunction "2_2") (pintype "passive"))
      (node (ref "U$5") (pin "5") (pinfunction "I2C1_SCL/SPI0_TX/GP3_5") (pintype "bidirectional"))
    )
    (net (code "62") (name "Net-(U$5-I2C1_SDA{slash}SPI0_SCK{slash}GP2)") (class "Default")
      (node (ref "SJ3") (pin "2") (pinfunction "2_2") (pintype "passive"))
      (node (ref "U$5") (pin "4") (pinfunction "I2C1_SDA/SPI0_SCK/GP2_4") (pintype "bidirectional"))
    )
    (net (code "63") (name "Net-(U$5-UART1_TX{slash}I2C0_SDA{slash}SPI0_RX{slash}GP4)") (class "Default")
      (node (ref "SJ2") (pin "2") (pinfunction "2_2") (pintype "passive"))
      (node (ref "U$5") (pin "6") (pinfunction "UART1_TX/I2C0_SDA/SPI0_RX/GP4_6") (pintype "bidirectional"))
    )
    (net (code "64") (name "Net-(U1-D)") (class "Default")
      (node (ref "J12") (pin "3") (pinfunction "3_3") (pintype "passive"))
      (node (ref "R10") (pin "1") (pinfunction "1_1") (pintype "passive"))
      (node (ref "U1") (pin "3") (pinfunction "D_3") (pintype "passive"))
    )
    (net (code "65") (name "Net-(U1-G)") (class "Default")
      (node (ref "R3") (pin "1") (pinfunction "1_1") (pintype "passive"))
      (node (ref "R7") (pin "2") (pinfunction "2_2") (pintype "passive"))
      (node (ref "U1") (pin "1") (pinfunction "G_1") (pintype "passive"))
    )
    (net (code "66") (name "Net-(U3-D)") (class "Default")
      (node (ref "J13") (pin "2") (pinfunction "2_2") (pintype "passive"))
      (node (ref "LED6") (pin "C") (pinfunction "C_C") (pintype "passive"))
      (node (ref "U3") (pin "3") (pinfunction "D_3") (pintype "passive"))
      (node (ref "U4") (pin "3") (pinfunction "D_3") (pintype "passive"))
    )
    (net (code "67") (name "Net-(U3-G)") (class "Default")
      (node (ref "R13") (pin "1") (pinfunction "1_1") (pintype "passive"))
      (node (ref "R14") (pin "2") (pinfunction "2_2") (pintype "passive"))
      (node (ref "U3") (pin "1") (pinfunction "G_1") (pintype "passive"))
      (node (ref "U4") (pin "1") (pinfunction "G_1") (pintype "passive"))
    )
    (net (code "68") (name "Net-(U5-D)") (class "Default")
      (node (ref "J14") (pin "2") (pinfunction "2_2") (pintype "passive"))
      (node (ref "R23") (pin "1") (pinfunction "1_1") (pintype "passive"))
      (node (ref "U5") (pin "3") (pinfunction "D_3") (pintype "passive"))
    )
    (net (code "69") (name "Net-(U5-G)") (class "Default")
      (node (ref "R21") (pin "1") (pinfunction "1_1") (pintype "passive"))
      (node (ref "R22") (pin "2") (pinfunction "2_2") (pintype "passive"))
      (node (ref "U5") (pin "1") (pinfunction "G_1") (pintype "passive"))
    )
    (net (code "70") (name "Net-(U7-BOOT)") (class "Default")
      (node (ref "C6") (pin "1") (pinfunction "1_1") (pintype "passive"))
      (node (ref "U7") (pin "6") (pinfunction "BOOT_6") (pintype "power_in"))
    )
    (net (code "71") (name "Net-(U7-FB)") (class "Default")
      (node (ref "C7") (pin "2") (pinfunction "2_2") (pintype "passive"))
      (node (ref "R24") (pin "1") (pinfunction "1_1") (pintype "passive"))
      (node (ref "R29") (pin "2") (pinfunction "2_2") (pintype "passive"))
      (node (ref "U7") (pin "4") (pinfunction "FB_4") (pintype "input"))
    )
    (net (code "72") (name "Net-(U7-SW)") (class "Default")
      (node (ref "C6") (pin "2") (pinfunction "2_2") (pintype "passive"))
      (node (ref "L1") (pin "2") (pinfunction "2_2") (pintype "passive"))
      (node (ref "U7") (pin "2") (pinfunction "SW_2") (pintype "power_in"))
    )
    (net (code "73") (name "unconnected-(J15-Pad3)") (class "Default")
      (node (ref "J15") (pin "3") (pinfunction "3_3") (pintype "passive"))
    )
    (net (code "74") (name "unconnected-(SV1-Pad1)") (class "Default")
      (node (ref "SV1") (pin "1") (pinfunction "1_1") (pintype "passive"))
    )
    (net (code "75") (name "unconnected-(SV1-Pad3)") (class "Default")
      (node (ref "SV1") (pin "3") (pinfunction "3_3") (pintype "passive"))
    )
    (net (code "76") (name "unconnected-(SV1-Pad5)") (class "Default")
      (node (ref "SV1") (pin "5") (pinfunction "5_5") (pintype "passive"))
    )
    (net (code "77") (name "unconnected-(SV1-Pad7)") (class "Default")
      (node (ref "SV1") (pin "7") (pinfunction "7_7") (pintype "passive"))
    )
    (net (code "78") (name "unconnected-(SV1-Pad11)") (class "Default")
      (node (ref "SV1") (pin "11") (pinfunction "11_11") (pintype "passive"))
    )
    (net (code "79") (name "unconnected-(SV1-Pad12)") (class "Default")
      (node (ref "SV1") (pin "12") (pinfunction "12_12") (pintype "passive"))
    )
    (net (code "80") (name "unconnected-(SV1-Pad13)") (class "Default")
      (node (ref "SV1") (pin "13") (pinfunction "13_13") (pintype "passive"))
    )
    (net (code "81") (name "unconnected-(SV1-Pad15)") (class "Default")
      (node (ref "SV1") (pin "15") (pinfunction "15_15") (pintype "passive"))
    )
    (net (code "82") (name "unconnected-(SV1-Pad16)") (class "Default")
      (node (ref "SV1") (pin "16") (pinfunction "16_16") (pintype "passive"))
    )
    (net (code "83") (name "unconnected-(SV1-Pad17)") (class "Default")
      (node (ref "SV1") (pin "17") (pinfunction "17_17") (pintype "passive"))
    )
    (net (code "84") (name "unconnected-(SV1-Pad18)") (class "Default")
      (node (ref "SV1") (pin "18") (pinfunction "18_18") (pintype "passive"))
    )
    (net (code "85") (name "unconnected-(SV1-Pad19)") (class "Default")
      (node (ref "SV1") (pin "19") (pinfunction "19_19") (pintype "passive"))
    )
    (net (code "86") (name "unconnected-(SV1-Pad21)") (class "Default")
      (node (ref "SV1") (pin "21") (pinfunction "21_21") (pintype "passive"))
    )
    (net (code "87") (name "unconnected-(SV1-Pad22)") (class "Default")
      (node (ref "SV1") (pin "22") (pinfunction "22_22") (pintype "passive"))
    )
    (net (code "88") (name "unconnected-(SV1-Pad23)") (class "Default")
      (node (ref "SV1") (pin "23") (pinfunction "23_23") (pintype "passive"))
    )
    (net (code "89") (name "unconnected-(SV1-Pad24)") (class "Default")
      (node (ref "SV1") (pin "24") (pinfunction "24_24") (pintype "passive"))
    )
    (net (code "90") (name "unconnected-(SV1-Pad26)") (class "Default")
      (node (ref "SV1") (pin "26") (pinfunction "26_26") (pintype "passive"))
    )
    (net (code "91") (name "unconnected-(SV1-Pad27)") (class "Default")
      (node (ref "SV1") (pin "27") (pinfunction "27_27") (pintype "passive"))
    )
    (net (code "92") (name "unconnected-(SV1-Pad28)") (class "Default")
      (node (ref "SV1") (pin "28") (pinfunction "28_28") (pintype "passive"))
    )
    (net (code "93") (name "unconnected-(SV1-Pad29)") (class "Default")
      (node (ref "SV1") (pin "29") (pinfunction "29_29") (pintype "passive"))
    )
    (net (code "94") (name "unconnected-(SV1-Pad31)") (class "Default")
      (node (ref "SV1") (pin "31") (pinfunction "31_31") (pintype "passive"))
    )
    (net (code "95") (name "unconnected-(SV1-Pad32)") (class "Default")
      (node (ref "SV1") (pin "32") (pinfunction "32_32") (pintype "passive"))
    )
    (net (code "96") (name "unconnected-(SV1-Pad33)") (class "Default")
      (node (ref "SV1") (pin "33") (pinfunction "33_33") (pintype "passive"))
    )
    (net (code "97") (name "unconnected-(SV1-Pad35)") (class "Default")
      (node (ref "SV1") (pin "35") (pinfunction "35_35") (pintype "passive"))
    )
    (net (code "98") (name "unconnected-(SV1-Pad36)") (class "Default")
      (node (ref "SV1") (pin "36") (pinfunction "36_36") (pintype "passive"))
    )
    (net (code "99") (name "unconnected-(SV1-Pad37)") (class "Default")
      (node (ref "SV1") (pin "37") (pinfunction "37_37") (pintype "passive"))
    )
    (net (code "100") (name "unconnected-(SV1-Pad38)") (class "Default")
      (node (ref "SV1") (pin "38") (pinfunction "38_38") (pintype "passive"))
    )
    (net (code "101") (name "unconnected-(SV1-Pad40)") (class "Default")
      (node (ref "SV1") (pin "40") (pinfunction "40_40") (pintype "passive"))
    )
    (net (code "102") (name "unconnected-(SV5-Pad3)") (class "Default")
      (node (ref "SV5") (pin "3") (pinfunction "3_3") (pintype "passive"))
    )
    (net (code "103") (name "unconnected-(SV5-Pad21)") (class "Default")
      (node (ref "SV5") (pin "21") (pinfunction "21_21") (pintype "passive"))
    )
    (net (code "104") (name "unconnected-(SV5-Pad22)") (class "Default")
      (node (ref "SV5") (pin "22") (pinfunction "22_22") (pintype "passive"))
    )
    (net (code "105") (name "unconnected-(SV5-Pad23)") (class "Default")
      (node (ref "SV5") (pin "23") (pinfunction "23_23") (pintype "passive"))
    )
    (net (code "106") (name "unconnected-(U$5-3V3(OUT)-Pad36)") (class "Default")
      (node (ref "U$5") (pin "36") (pinfunction "3V3(OUT)_36") (pintype "output"))
    )
    (net (code "107") (name "unconnected-(U$5-RUN-Pad30)") (class "Default")
      (node (ref "U$5") (pin "30") (pinfunction "RUN_30") (pintype "passive"))
    )
    (net (code "108") (name "unconnected-(U7-EN-Pad5)") (class "Default")
      (node (ref "U7") (pin "5") (pinfunction "EN_5") (pintype "input"))
    )
  )
)
